# REG.net
KiCad netlist of a schematic drawn in Altium Designer
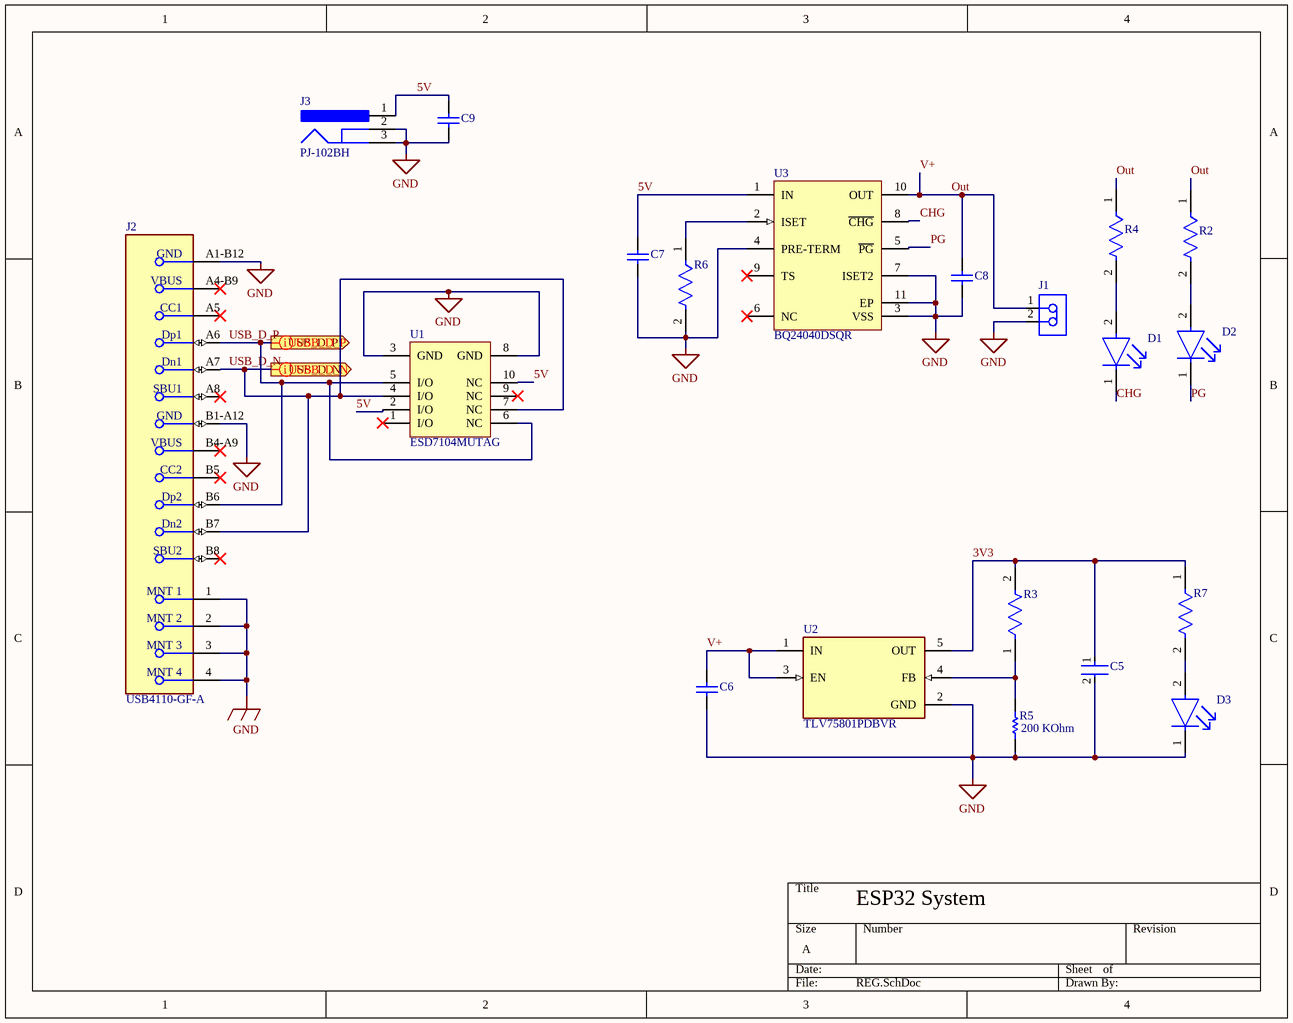
[diagram p0: REG.SchDoc]

(export (version "E")
  (design (tool "Eeschema 10.0.6"))
  (components
    (comp (ref "C5")
      (value "GRM188Z71A106KA73J")
      (footprint "FP-GRM188-0_2-IPC_B")
      (description "Chip Multilayer Ceramic Capacitors for General Purpose, 0603, 10uF, X7R, 15%, 10%, 10V")
      (libsource (lib "Altium Content Vault") (part "11868f565c42a9108669ba33697ecf6"))
    )
    (comp (ref "C6")
      (value "C0603C105K4RACTU")
      (footprint "CAPC1608X90X35LL15T15")
      (fields (field (name "MANUFACTURER") "Kemet"))
      (libsource (lib "Altium Content Vault") (part "CAP"))
    )
    (comp (ref "C7")
      (value "C0603C105K4RACTU")
      (footprint "CAPC1608X90X35LL15T15")
      (fields (field (name "MANUFACTURER") "Kemet"))
      (libsource (lib "Altium Content Vault") (part "CAP"))
    )
    (comp (ref "C8")
      (value "C0603C105K4RACTU")
      (footprint "CAPC1608X90X35LL15T15")
      (fields (field (name "MANUFACTURER") "Kemet"))
      (libsource (lib "Altium Content Vault") (part "CAP"))
    )
    (comp (ref "C9")
      (value "C0603C105K4RACTU")
      (footprint "CAPC1608X90X35LL15T15")
      (fields (field (name "MANUFACTURER") "Kemet"))
      (libsource (lib "Altium Content Vault") (part "CAP"))
    )
    (comp (ref "D1")
      (value "LTST-C230EKT")
      (footprint "FP-LTST-C230EKT-MFG")
      (description "LED RED CLEAR CHIP SMD")
      (libsource (lib "Altium Content Vault") (part "8706943c75ba83719d021d2fdc84c58"))
    )
    (comp (ref "D2")
      (value "APT1608ZGCK")
      (footprint "FP-APT1608ZGCK-MFG")
      (description "LED GREEN CLEAR CHIP SMD")
      (libsource (lib "Altium Content Vault") (part "8706943c75ba83719d021d2fdc84c58"))
    )
    (comp (ref "D3")
      (value "APT1608ZGCK")
      (footprint "FP-APT1608ZGCK-MFG")
      (description "LED GREEN CLEAR CHIP SMD")
      (libsource (lib "Altium Content Vault") (part "8706943c75ba83719d021d2fdc84c58"))
    )
    (comp (ref "J1")
      (value "B2B-PH-K-S(LF)(SN)")
      (footprint "JST-B2B-PH-K-S_V")
      (fields (field (name "MANUFACTURER") "JST"))
      (libsource (lib "Altium Content Vault") (part "CN-2P-F-QF2"))
    )
    (comp (ref "J2")
      (value "USB4110-GF-A")
      (footprint "FP-USB4110-GF-A-MFG")
      (description "CONN USB 2.0 TYPE-C R/A SMT")
      (fields
        (field (name "OCTOPART") "https://octopart.com/usb4110-gf-a-gct-103941985")
        (field (name "MANUFACTURER") "GCT")
      )
      (libsource (lib "Altium Content Vault") (part "e23f2b38bb3c3f98e683ebab9ede730"))
    )
    (comp (ref "J3")
      (value "PJ-102BH")
      (footprint "CUI-PJ-102BH_V")
      (fields (field (name "MANUFACTURER") "CUIInc."))
      (libsource (lib "Altium Content Vault") (part "JACK-2CD3-RN"))
    )
    (comp (ref "R2")
      (value "RN73R1JTTD1501B25")
      (footprint "FP-RN73R1J-IPC_A")
      (description "1.5kΩ ±0.1% 0.1W, 1/10W Chip Resistor 0603 (1608 Metric) Moisture Resistant Thin Film")
      (libsource (lib "Altium Content Vault") (part "1029c3af85768c4190bb7ad29bc67b5"))
    )
    (comp (ref "R3")
      (value "AT0603BRD0740KL")
      (footprint "FP-AT0603-IPC_B")
      (description "Thin Film Chip Resistors Automotive Grade 40kΩ 0.1% 25ppm/°C 0603")
      (libsource (lib "Altium Content Vault") (part "1029c3af85768c4190bb7ad29bc67b5"))
    )
    (comp (ref "R4")
      (value "RN73R1JTTD1501B25")
      (footprint "FP-RN73R1J-IPC_A")
      (description "1.5kΩ ±0.1% 0.1W, 1/10W Chip Resistor 0603 (1608 Metric) Moisture Resistant Thin Film")
      (libsource (lib "Altium Content Vault") (part "1029c3af85768c4190bb7ad29bc67b5"))
    )
    (comp (ref "R5")
      (value "ERJ-2RKF2003X")
      (footprint "RESC1005X40X25NL05T05")
      (description "Chip Resistor, 200 KOhm, +/- 1%, 100 mW, -55 to 155 degC, 0402 (1005 Metric), RoHS, Tape and Reel")
      (fields
        (field (name "TOLERANCE") "1%")
        (field (name "MANUFACTURER") "Basic Passives")
        (field (name "RESISTANCE") "200 KOhm")
      )
      (libsource (lib "Altium Content Vault") (part "RES-2"))
    )
    (comp (ref "R6")
      (value "CRGCQ0402J1K0")
      (footprint "FP-CRGCQ0402-IPC_C")
      (description "CRGCQ 0402 1K0 5%")
      (fields (field (name "TOLERANCE") "0.05") (field (name "MANUFACTURER") "TE Connectivity"))
      (libsource (lib "Altium Content Vault") (part "1029c3af85768c4190bb7ad29bc67b5"))
    )
    (comp (ref "R7")
      (value "TFCR0402-16W-E-1001DT")
      (footprint "FP-TFCR0402-IPC_A")
      (description "RES Thin Film,  1kΩ, 0.5%, 0.063W, 25ppm/°C, 0402")
      (libsource (lib "Altium Content Vault") (part "1029c3af85768c4190bb7ad29bc67b5"))
    )
    (comp (ref "U1")
      (value "ESD7104MUTAG")
      (footprint "ONSC-UDFN-10-517BB-01_V")
      (fields (field (name "MANUFACTURER") "On Semiconductor"))
      (libsource (lib "Altium Content Vault") (part "ONSC-ESD7104-UDFN-10-517BB-01"))
    )
    (comp (ref "U2")
      (value "TLV75801PDBVR")
      (footprint "FP-DBV0005A-IPC_C")
      (description "IC POWER MANAGEMENT SUPERVISORY")
      (libsource (lib "Altium Content Vault") (part "ed3a5c7a2f2d19c5e1dcfd7dcd5e996"))
    )
    (comp (ref "U3")
      (value "BQ24040DSQR")
      (footprint "DSQ0010A_V")
      (fields (field (name "MANUFACTURER") "Texas Instruments"))
      (libsource (lib "Altium Content Vault") (part "TI-BQ24040DSQ10-1500X900TP"))
    )
  )
  (nets
    (net (code "1") (name "/3V3") (class "Default")
      (node (ref "C5") (pin "1") (pinfunction "1_1") (pintype "passive"))
      (node (ref "R3") (pin "2") (pinfunction "2_2") (pintype "passive"))
      (node (ref "R7") (pin "1") (pinfunction "1_1") (pintype "passive"))
      (node (ref "U2") (pin "5") (pinfunction "OUT_5") (pintype "passive"))
    )
    (net (code "2") (name "/5V") (class "Default")
      (node (ref "C7") (pin "2") (pinfunction "2_2") (pintype "passive"))
      (node (ref "C9") (pin "2") (pinfunction "2_2") (pintype "passive"))
      (node (ref "J3") (pin "1") (pinfunction "1_1") (pintype "passive"))
      (node (ref "U1") (pin "10") (pinfunction "NC_10") (pintype "passive"))
      (node (ref "U1") (pin "2") (pinfunction "I/O_2") (pintype "passive"))
      (node (ref "U3") (pin "1") (pinfunction "IN_1") (pintype "power_in"))
    )
    (net (code "3") (name "/CHG") (class "Default")
      (node (ref "D1") (pin "1") (pinfunction "C_1") (pintype "passive"))
      (node (ref "U3") (pin "8") (pinfunction "~{CHG}_8") (pintype "tri_state"))
    )
    (net (code "4") (name "/Out") (class "Default")
      (node (ref "C6") (pin "2") (pinfunction "2_2") (pintype "passive"))
      (node (ref "C8") (pin "2") (pinfunction "2_2") (pintype "passive"))
      (node (ref "J1") (pin "1") (pinfunction "1_1") (pintype "passive"))
      (node (ref "R2") (pin "1") (pinfunction "1_1") (pintype "passive"))
      (node (ref "R4") (pin "1") (pinfunction "1_1") (pintype "passive"))
      (node (ref "U2") (pin "1") (pinfunction "IN_1") (pintype "power_in"))
      (node (ref "U2") (pin "3") (pinfunction "EN_3") (pintype "input"))
      (node (ref "U3") (pin "10") (pinfunction "OUT_10") (pintype "power_in"))
    )
    (net (code "5") (name "/PG") (class "Default")
      (node (ref "D2") (pin "1") (pinfunction "C_1") (pintype "passive"))
      (node (ref "U3") (pin "5") (pinfunction "~{PG}_5") (pintype "tri_state"))
    )
    (net (code "6") (name "/USB_D_N") (class "Default")
      (node (ref "J2") (pin "A7") (pinfunction "Dn1_A7") (pintype "bidirectional"))
      (node (ref "J2") (pin "B7") (pinfunction "Dn2_B7") (pintype "bidirectional"))
      (node (ref "U1") (pin "4") (pinfunction "I/O_4") (pintype "passive"))
      (node (ref "U1") (pin "7") (pinfunction "NC_7") (pintype "passive"))
    )
    (net (code "7") (name "/USB_D_P") (class "Default")
      (node (ref "J2") (pin "A6") (pinfunction "Dp1_A6") (pintype "bidirectional"))
      (node (ref "J2") (pin "B6") (pinfunction "Dp2_B6") (pintype "bidirectional"))
      (node (ref "U1") (pin "5") (pinfunction "I/O_5") (pintype "passive"))
      (node (ref "U1") (pin "6") (pinfunction "NC_6") (pintype "passive"))
    )
    (net (code "8") (name "GND") (class "Default")
      (node (ref "C5") (pin "2") (pinfunction "2_2") (pintype "passive"))
      (node (ref "C6") (pin "1") (pinfunction "1_1") (pintype "passive"))
      (node (ref "C7") (pin "1") (pinfunction "1_1") (pintype "passive"))
      (node (ref "C8") (pin "1") (pinfunction "1_1") (pintype "passive"))
      (node (ref "C9") (pin "1") (pinfunction "1_1") (pintype "passive"))
      (node (ref "D3") (pin "1") (pinfunction "C_1") (pintype "passive"))
      (node (ref "J1") (pin "2") (pinfunction "2_2") (pintype "passive"))
      (node (ref "J2") (pin "1") (pinfunction "MNT_1_1") (pintype "passive"))
      (node (ref "J2") (pin "2") (pinfunction "MNT_2_2") (pintype "passive"))
      (node (ref "J2") (pin "3") (pinfunction "MNT_3_3") (pintype "passive"))
      (node (ref "J2") (pin "4") (pinfunction "MNT_4_4") (pintype "passive"))
      (node (ref "J2") (pin "A1-B12") (pinfunction "GND_A1-B12") (pintype "passive"))
      (node (ref "J2") (pin "B1-A12") (pinfunction "GND_B1-A12") (pintype "bidirectional"))
      (node (ref "J3") (pin "2") (pinfunction "2_2") (pintype "passive"))
      (node (ref "J3") (pin "3") (pinfunction "3_3") (pintype "passive"))
      (node (ref "R5") (pin "1") (pinfunction "1_1") (pintype "passive"))
      (node (ref "R6") (pin "2") (pinfunction "2_2") (pintype "passive"))
      (node (ref "U1") (pin "3") (pinfunction "GND_3") (pintype "power_in"))
      (node (ref "U1") (pin "8") (pinfunction "GND_8") (pintype "power_in"))
      (node (ref "U2") (pin "2") (pinfunction "GND_2") (pintype "power_in"))
      (node (ref "U3") (pin "11") (pinfunction "EP_11") (pintype "power_in"))
      (node (ref "U3") (pin "3") (pinfunction "VSS_3") (pintype "power_in"))
      (node (ref "U3") (pin "4") (pinfunction "PRE-TERM_4") (pintype "passive"))
      (node (ref "U3") (pin "7") (pinfunction "ISET2_7") (pintype "passive"))
    )
    (net (code "9") (name "Net-(D1-A)") (class "Default")
      (node (ref "D1") (pin "2") (pinfunction "A_2") (pintype "passive"))
      (node (ref "R4") (pin "2") (pinfunction "2_2") (pintype "passive"))
    )
    (net (code "10") (name "Net-(D2-A)") (class "Default")
      (node (ref "D2") (pin "2") (pinfunction "A_2") (pintype "passive"))
      (node (ref "R2") (pin "2") (pinfunction "2_2") (pintype "passive"))
    )
    (net (code "11") (name "Net-(D3-A)") (class "Default")
      (node (ref "D3") (pin "2") (pinfunction "A_2") (pintype "passive"))
      (node (ref "R7") (pin "2") (pinfunction "2_2") (pintype "passive"))
    )
    (net (code "12") (name "Net-(U2-FB)") (class "Default")
      (node (ref "R3") (pin "1") (pinfunction "1_1") (pintype "passive"))
      (node (ref "R5") (pin "2") (pinfunction "2_2") (pintype "passive"))
      (node (ref "U2") (pin "4") (pinfunction "FB_4") (pintype "input"))
    )
    (net (code "13") (name "Net-(U3-ISET)") (class "Default")
      (node (ref "R6") (pin "1") (pinfunction "1_1") (pintype "passive"))
      (node (ref "U3") (pin "2") (pinfunction "ISET_2") (pintype "input"))
    )
    (net (code "14") (name "unconnected-(J2-CC1-PadA5)") (class "Default")
      (node (ref "J2") (pin "A5") (pinfunction "CC1_A5") (pintype "power_in+no_connect"))
    )
    (net (code "15") (name "unconnected-(J2-CC2-PadB5)") (class "Default")
      (node (ref "J2") (pin "B5") (pinfunction "CC2_B5") (pintype "power_in+no_connect"))
    )
    (net (code "16") (name "unconnected-(J2-SBU1-PadA8)") (class "Default")
      (node (ref "J2") (pin "A8") (pinfunction "SBU1_A8") (pintype "bidirectional+no_connect"))
    )
    (net (code "17") (name "unconnected-(J2-SBU2-PadB8)") (class "Default")
      (node (ref "J2") (pin "B8") (pinfunction "SBU2_B8") (pintype "bidirectional+no_connect"))
    )
    (net (code "18") (name "unconnected-(J2-VBUS-PadA4-B9)") (class "Default")
      (node (ref "J2") (pin "A4-B9") (pinfunction "VBUS_A4-B9") (pintype "power_in+no_connect"))
    )
    (net (code "19") (name "unconnected-(J2-VBUS-PadB4-A9)") (class "Default")
      (node (ref "J2") (pin "B4-A9") (pinfunction "VBUS_B4-A9") (pintype "power_in+no_connect"))
    )
    (net (code "20") (name "unconnected-(U1-I{slash}O-Pad1)") (class "Default")
      (node (ref "U1") (pin "1") (pinfunction "I/O_1") (pintype "passive+no_connect"))
    )
    (net (code "21") (name "unconnected-(U1-NC-Pad9)") (class "Default")
      (node (ref "U1") (pin "9") (pinfunction "NC_9") (pintype "passive+no_connect"))
    )
    (net (code "22") (name "unconnected-(U3-NC-Pad6)") (class "Default")
      (node (ref "U3") (pin "6") (pinfunction "NC_6") (pintype "passive+no_connect"))
    )
    (net (code "23") (name "unconnected-(U3-TS-Pad9)") (class "Default")
      (node (ref "U3") (pin "9") (pinfunction "TS_9") (pintype "passive+no_connect"))
    )
  )
)
